# Diode_as_a_voltage_regulator.net
KiCad netlist of a schematic drawn in EAGLE
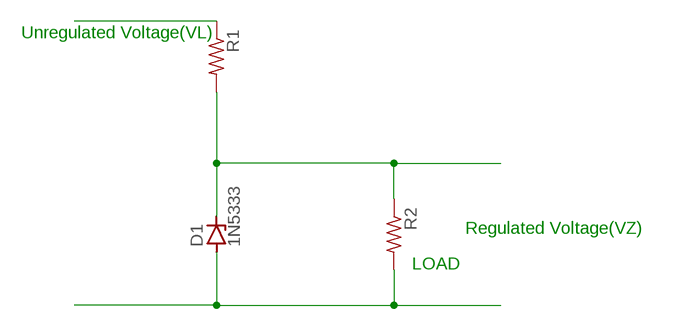
[diagram p0: schematic, sheet 1]

(export (version "E")
  (design (tool "Eeschema 10.0.6"))
  (components
    (comp (ref "D1")
      (value "1N5333")
      (footprint "eagle-import:C1702-15")
      (libsource (lib "eagle-import") (part "1N5333"))
    )
    (comp (ref "R1")
      (value "R-US_R0805")
      (footprint "eagle-import:R0805")
      (libsource (lib "eagle-import") (part "R-US_R0805"))
    )
    (comp (ref "R2")
      (value "R-US_R0805")
      (footprint "eagle-import:R0805")
      (libsource (lib "eagle-import") (part "R-US_R0805"))
    )
  )
  (nets
    (net (code "1") (name "Net-(D1-PadA)") (class "Default")
      (node (ref "D1") (pin "A") (pinfunction "A_A") (pintype "passive"))
      (node (ref "R2") (pin "2") (pinfunction "2_2") (pintype "passive"))
    )
    (net (code "2") (name "Net-(D1-PadC)") (class "Default")
      (node (ref "D1") (pin "C") (pinfunction "C_C") (pintype "passive"))
      (node (ref "R1") (pin "2") (pinfunction "2_2") (pintype "passive"))
      (node (ref "R2") (pin "1") (pinfunction "1_1") (pintype "passive"))
    )
    (net (code "3") (name "unconnected-(R1-Pad1)") (class "Default")
      (node (ref "R1") (pin "1") (pinfunction "1_1") (pintype "passive"))
    )
  )
)
